# 0228-carrier-pos-neg-boost.net
KiCad netlist of a schematic drawn in EAGLE
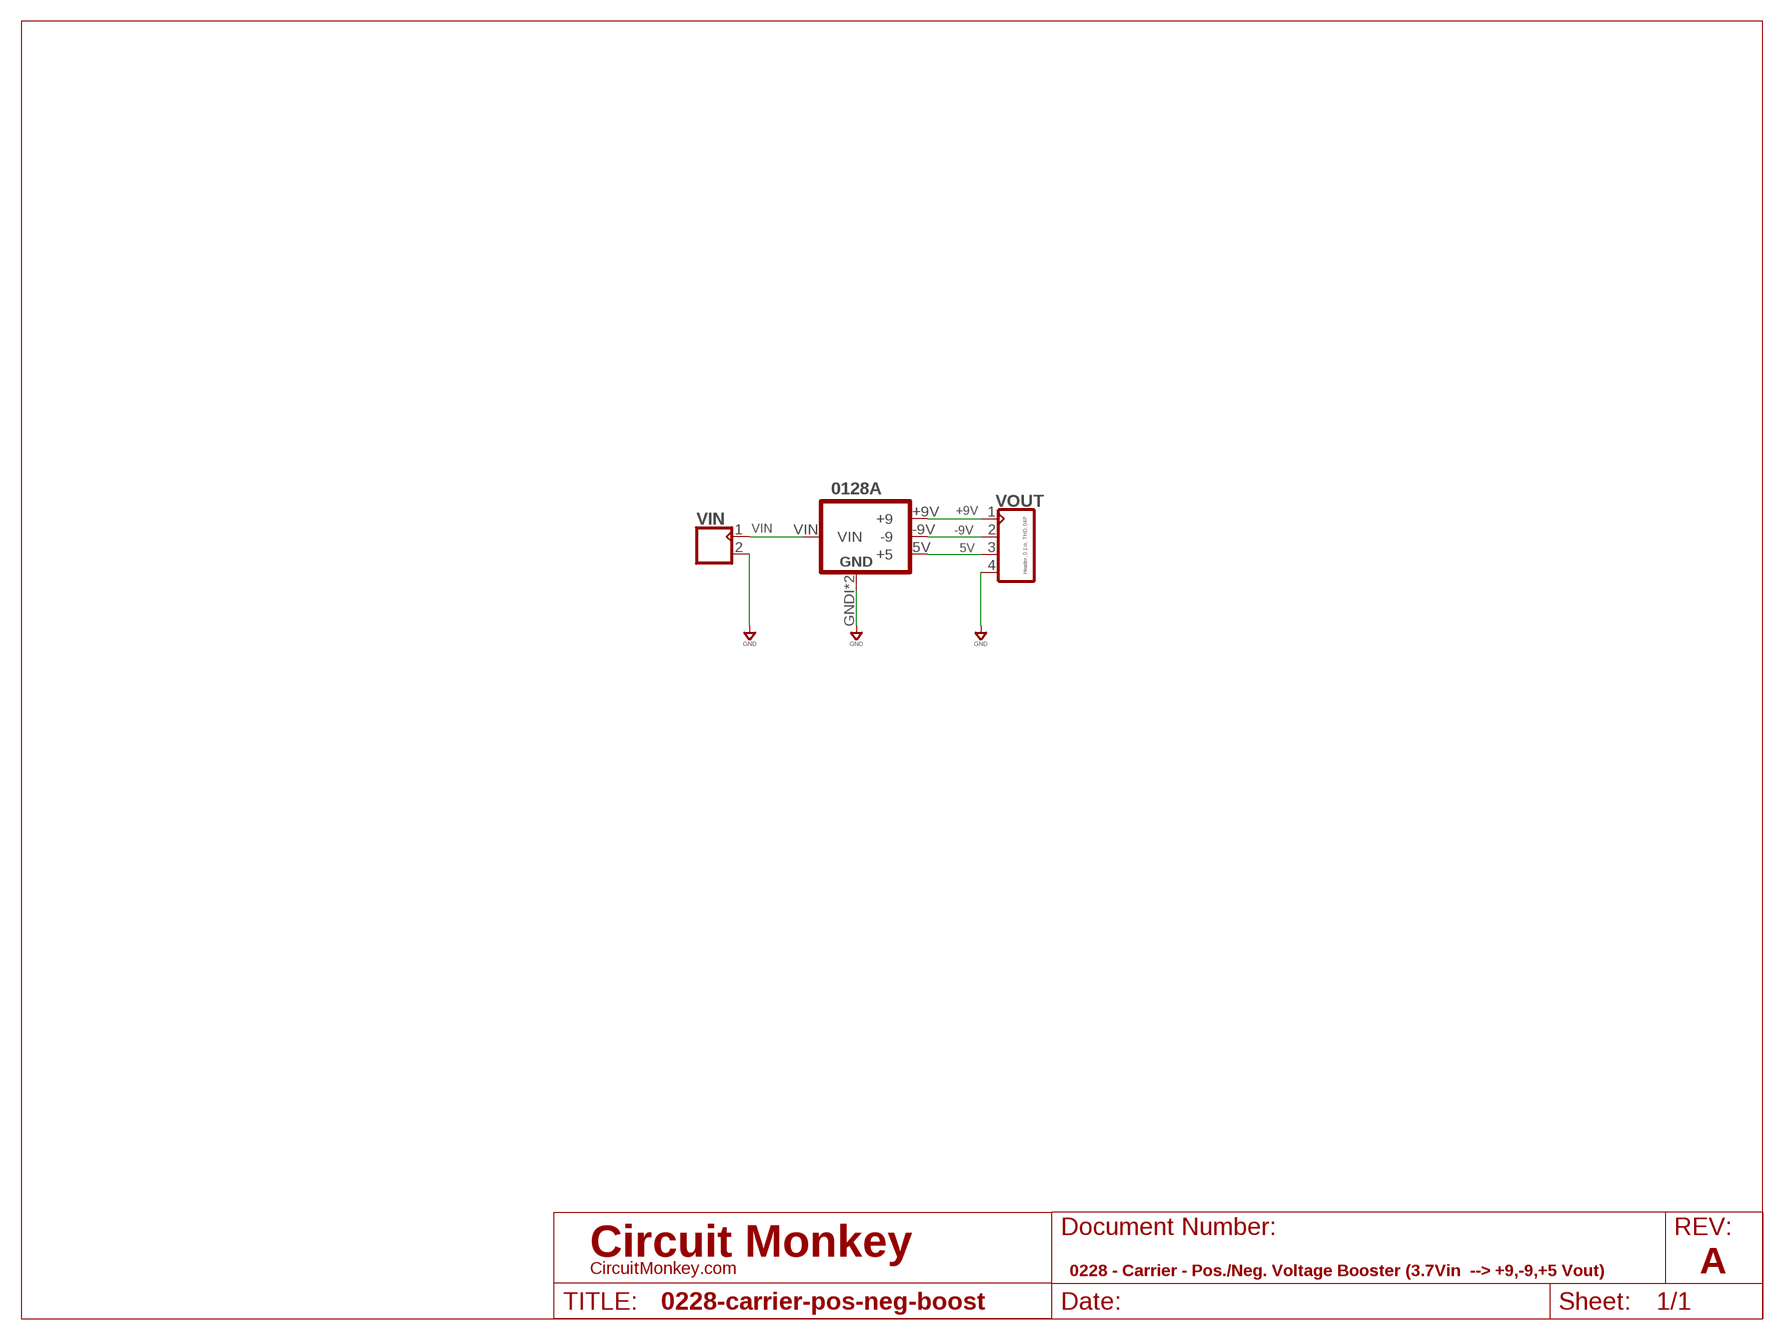
[diagram p0: schematic, sheet 1]

(export (version "E")
  (design (tool "Eeschema 10.0.6"))
  (components
    (comp (ref "0128A")
      (value "0128REV-A")
      (footprint "eagle-import:1028A")
      (libsource (lib "eagle-import") (part "0128REV-A"))
    )
    (comp (ref "VIN")
      (value "CON_02X1-2.54MM-THD-VT")
      (footprint "eagle-import:MA02X1-VT-THD")
      (libsource (lib "eagle-import") (part "CON_02X1-2.54MM-THD-VT"))
    )
    (comp (ref "VOUT")
      (value "Header, 0.1in, THD, 04P")
      (footprint "eagle-import:MA04X1-VT-THD")
      (fields (field (name "MFR") "Molex") (field (name "MPN") "022284043"))
      (libsource (lib "eagle-import") (part "CON_04X1-THD-VT"))
    )
  )
  (nets
    (net (code "1") (name "/+9V") (class "Default")
      (node (ref "0128A") (pin "+9V") (pinfunction "+9_+9V") (pintype "bidirectional"))
      (node (ref "VOUT") (pin "1") (pinfunction "1_1") (pintype "passive"))
    )
    (net (code "2") (name "/-9V") (class "Default")
      (node (ref "0128A") (pin "-9V") (pinfunction "-9_-9V") (pintype "bidirectional"))
      (node (ref "VOUT") (pin "2") (pinfunction "2_2") (pintype "passive"))
    )
    (net (code "3") (name "/5V") (class "Default")
      (node (ref "0128A") (pin "5V") (pinfunction "+5_5V") (pintype "bidirectional"))
      (node (ref "VOUT") (pin "3") (pinfunction "3_3") (pintype "passive"))
    )
    (net (code "4") (name "/VIN") (class "Default")
      (node (ref "0128A") (pin "VIN") (pinfunction "VIN_VIN") (pintype "bidirectional"))
      (node (ref "VIN") (pin "1") (pinfunction "1_1") (pintype "passive"))
    )
    (net (code "5") (name "GND") (class "Default")
      (node (ref "0128A") (pin "GNDI") (pinfunction "GND_GNDI") (pintype "bidirectional"))
      (node (ref "0128A") (pin "GNDO") (pinfunction "GND_GNDO") (pintype "bidirectional"))
      (node (ref "VIN") (pin "2") (pinfunction "2_2") (pintype "passive"))
      (node (ref "VOUT") (pin "4") (pinfunction "4_4") (pintype "passive"))
    )
  )
)
